# schematic.net
KiCad netlist of a schematic drawn in EasyEDA
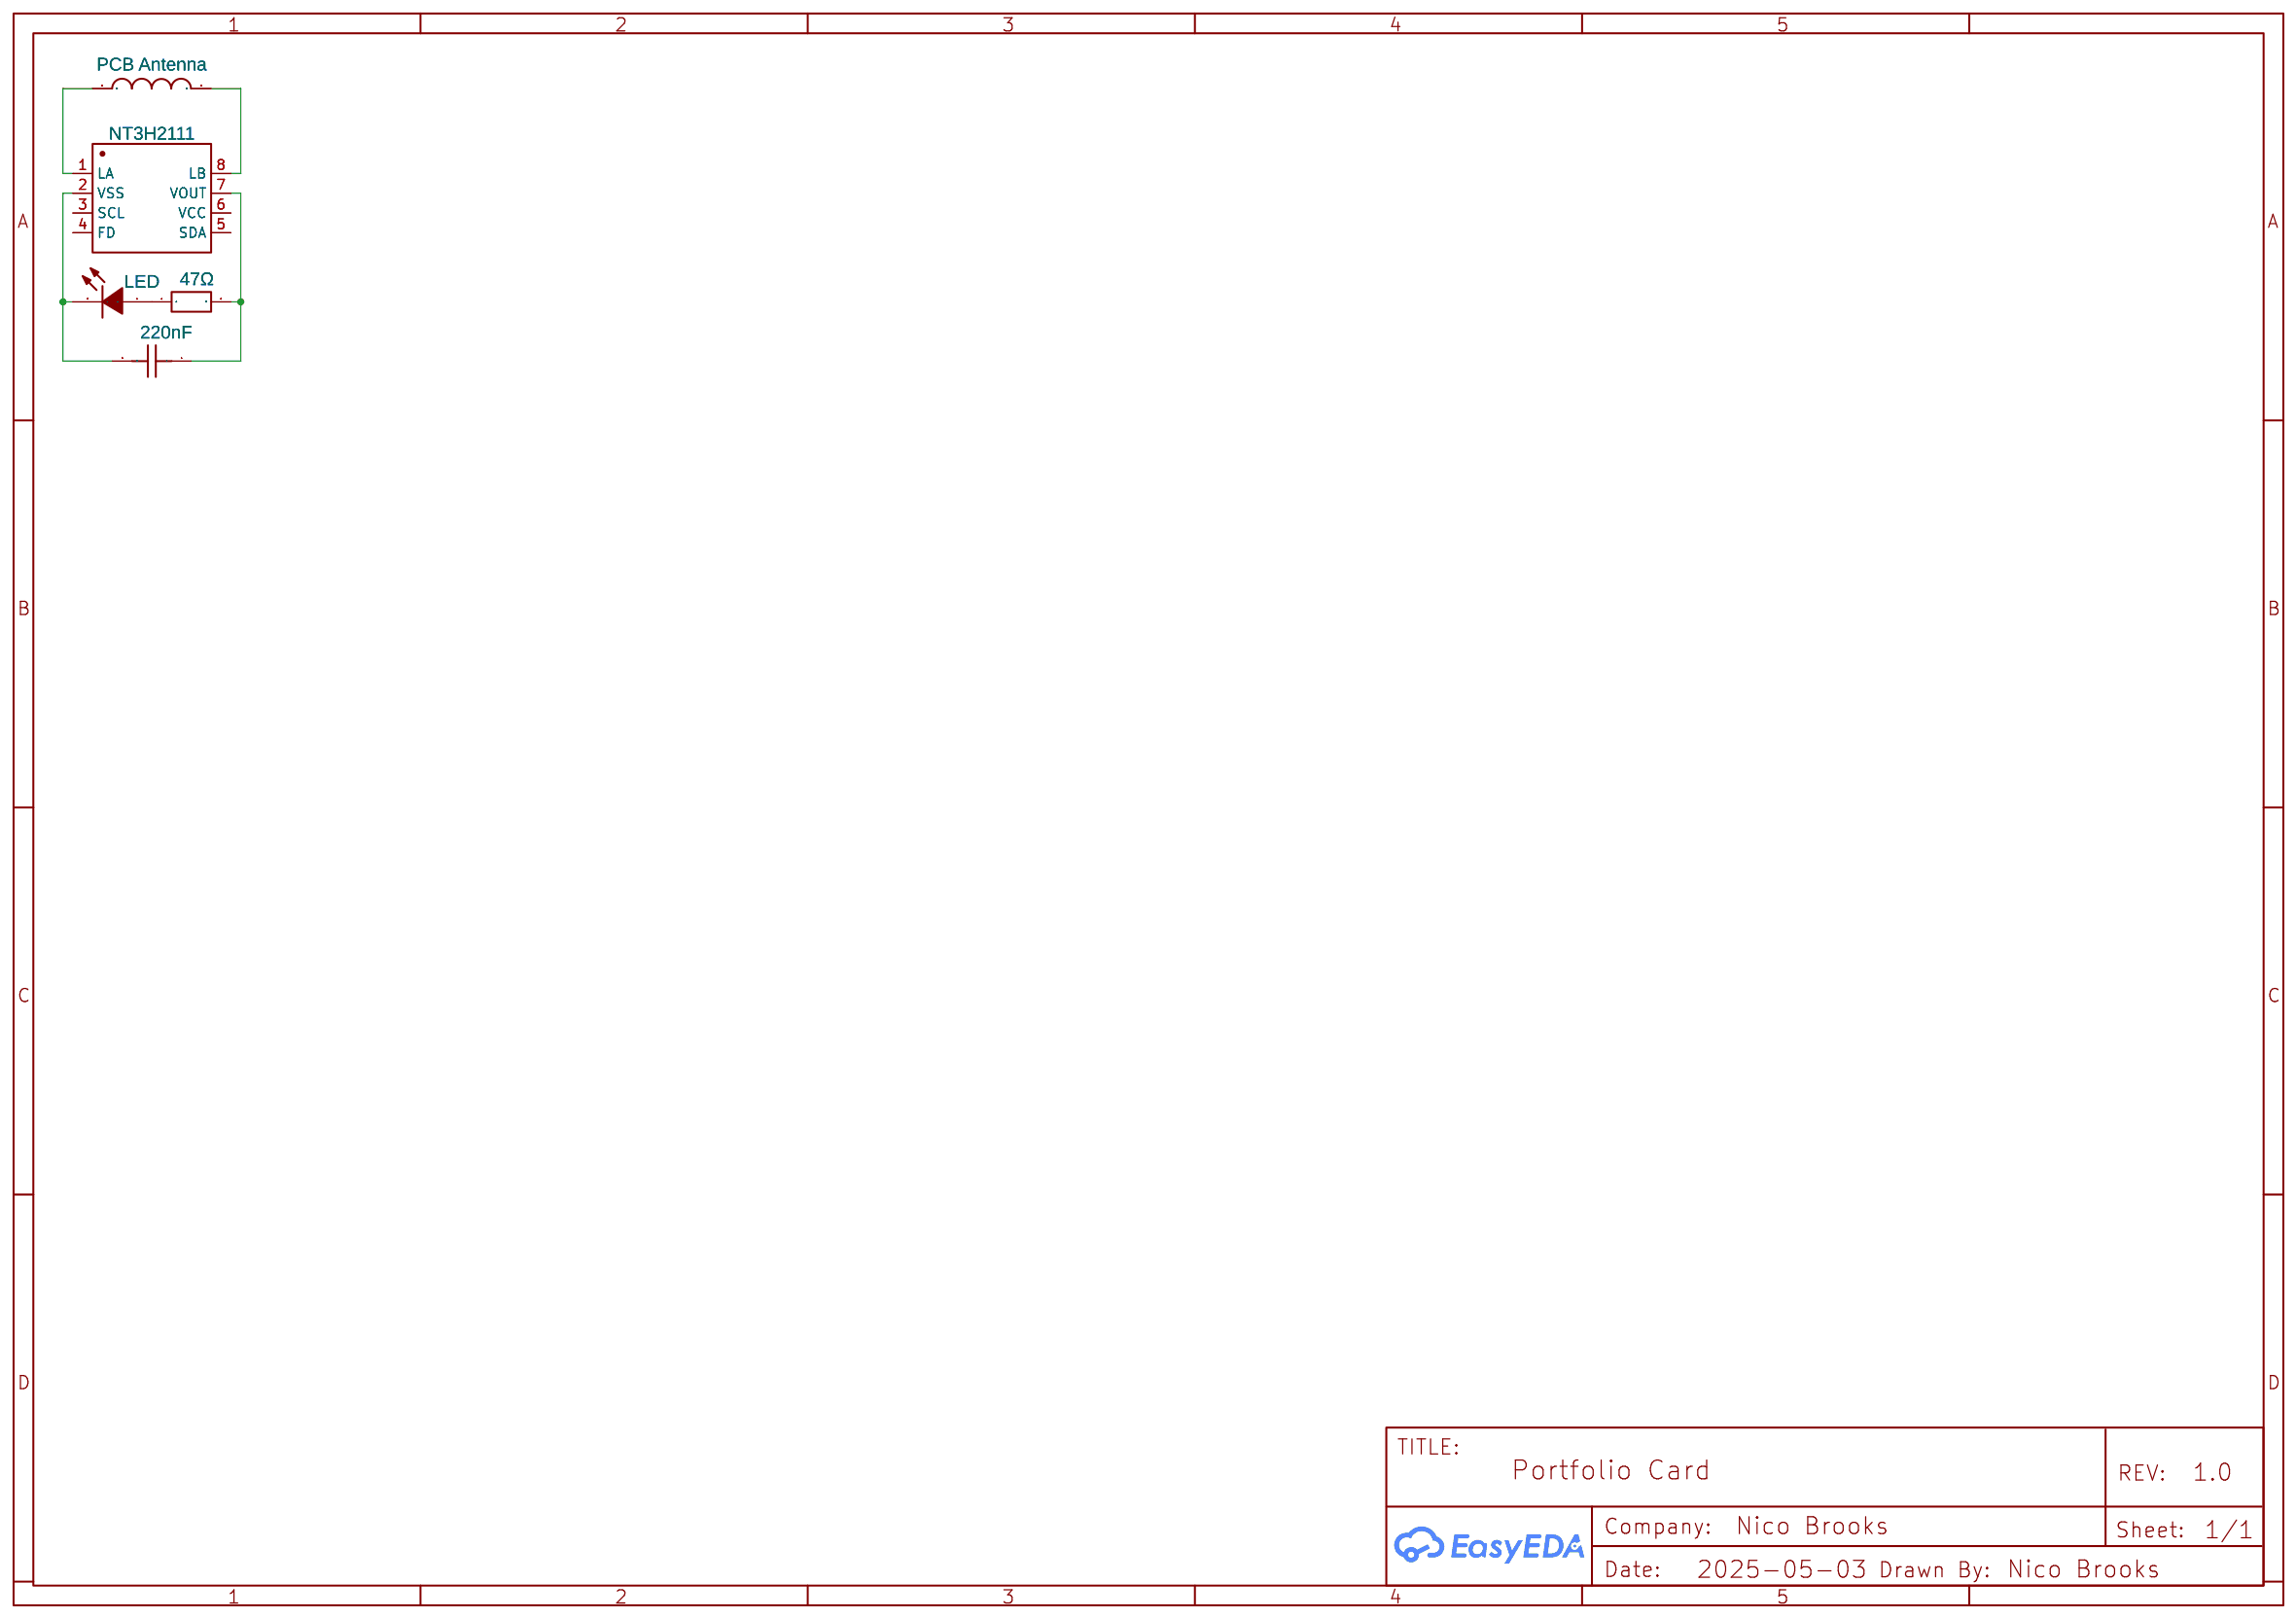
[diagram p0: schematic sheet]

(export (version "E")
  (design (tool "Eeschema 10.0.6"))
  (components
    (comp (ref "1") (value "PCB Antenna") (libsource (lib "") (part "25X48MM_NFC_ANTENNA")))
    (comp (ref "C1")
      (value "220nF")
      (fields
        (field (name "Manufacturer Part") "CL05A224KQ5NNNC")
        (field (name "Manufacturer") "SAMSUNG(三星)")
      )
      (libsource (lib "") (part "CL05A224KQ5NNNC"))
    )
    (comp (ref "LED")
      (value "17-21SUYC/TR8")
      (fields (field (name "Manufacturer Part") "KT-0805黄灯") (field (name "Manufacturer") "KENTO"))
      (libsource (lib "") (part "17-21SUYC/TR8"))
    )
    (comp (ref "R2")
      (value "47Ω")
      (fields
        (field (name "Manufacturer Part") "CR0805J47R0P05Z")
        (field (name "Manufacturer") "EVER OHMS(天二科技)")
      )
      (libsource (lib "") (part "CR0805J47R0P05Z"))
    )
    (comp (ref "U1")
      (value "NT3H2111")
      (fields (field (name "Manufacturer Part") "NT3H2111W0FHKH") (field (name "Manufacturer") "NXP(恩智浦)"))
      (libsource (lib "") (part "NT3H2111W0FHKH"))
    )
  )
  (nets
    (net (code "1") (name "Net-(LED-+)") (class "Default")
      (node (ref "LED") (pin "1") (pinfunction "+_1") (pintype "unspecified"))
      (node (ref "R2") (pin "1") (pinfunction "1_1") (pintype "unspecified"))
    )
    (net (code "2") (name "Net-(LED--)") (class "Default")
      (node (ref "C1") (pin "2") (pinfunction "2_2") (pintype "unspecified"))
      (node (ref "LED") (pin "2") (pinfunction "-_2") (pintype "unspecified"))
      (node (ref "U1") (pin "2") (pinfunction "VSS_2") (pintype "unspecified"))
    )
    (net (code "3") (name "Net-(U1-LA)") (class "Default")
      (node (ref "1") (pin "P$1") (pinfunction "P$1_P$1") (pintype "bidirectional"))
      (node (ref "U1") (pin "1") (pinfunction "LA_1") (pintype "unspecified"))
    )
    (net (code "4") (name "Net-(U1-LB)") (class "Default")
      (node (ref "1") (pin "P$2") (pinfunction "P$2_P$2") (pintype "bidirectional"))
      (node (ref "U1") (pin "8") (pinfunction "LB_8") (pintype "unspecified"))
    )
    (net (code "5") (name "Net-(U1-VOUT)") (class "Default")
      (node (ref "C1") (pin "1") (pinfunction "1_1") (pintype "unspecified"))
      (node (ref "R2") (pin "2") (pinfunction "2_2") (pintype "unspecified"))
      (node (ref "U1") (pin "7") (pinfunction "VOUT_7") (pintype "unspecified"))
    )
    (net (code "6") (name "unconnected-(U1-FD-Pad4)") (class "Default")
      (node (ref "U1") (pin "4") (pinfunction "FD_4") (pintype "unspecified"))
    )
    (net (code "7") (name "unconnected-(U1-SCL-Pad3)") (class "Default")
      (node (ref "U1") (pin "3") (pinfunction "SCL_3") (pintype "unspecified"))
    )
    (net (code "8") (name "unconnected-(U1-SDA-Pad5)") (class "Default")
      (node (ref "U1") (pin "5") (pinfunction "SDA_5") (pintype "unspecified"))
    )
    (net (code "9") (name "unconnected-(U1-VCC-Pad6)") (class "Default")
      (node (ref "U1") (pin "6") (pinfunction "VCC_6") (pintype "unspecified"))
    )
  )
)
